# CAN_Interface.net
KiCad netlist of a schematic drawn in Altium Designer
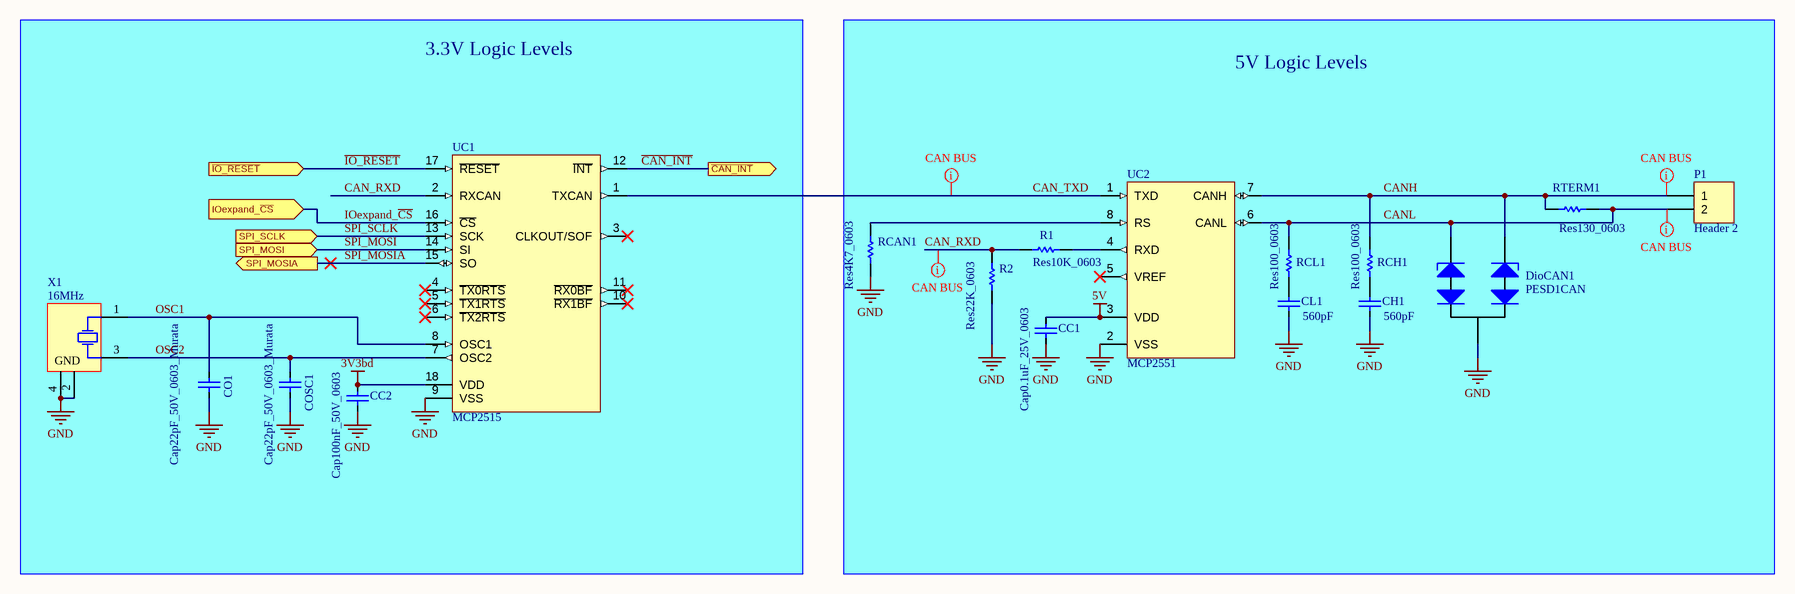
[diagram p0: CAN_Interface.SchDoc]

(export (version "E")
  (design (tool "Eeschema 10.0.6"))
  (components
    (comp (ref "CC1")
      (value "Cap0.1uF_25V_0603")
      (footprint "0603C_L")
      (libsource (lib " Advanced] Training Course - A365") (part "CAP General"))
    )
    (comp (ref "CC2")
      (value "Cap100nF_50V_0603")
      (footprint "0603C_L")
      (libsource (lib " Advanced] Training Course - A365") (part "CAP General"))
    )
    (comp (ref "CH1")
      (value "560pF")
      (footprint "0603C_L")
      (description "560pF 25V 0603")
      (fields (field (name "Comment") "CAP General"))
      (libsource (lib " Advanced] Training Course - A365") (part "CAP General"))
    )
    (comp (ref "CL1")
      (value "560pF")
      (footprint "0603C_L")
      (description "560pF 25V 0603")
      (fields (field (name "Comment") "CAP General"))
      (libsource (lib " Advanced] Training Course - A365") (part "CAP General"))
    )
    (comp (ref "CO1")
      (value "Cap22pF_50V_0603_Murata")
      (footprint "0603C_L")
      (fields (field (name "TOLERANCE") "5%"))
      (libsource (lib " Advanced] Training Course - A365") (part "CAP General"))
    )
    (comp (ref "COSC1")
      (value "Cap22pF_50V_0603_Murata")
      (footprint "0603C_L")
      (fields (field (name "TOLERANCE") "5%"))
      (libsource (lib " Advanced] Training Course - A365") (part "CAP General"))
    )
    (comp (ref "DioCAN1")
      (value "PESD1CAN")
      (footprint "SOT323")
      (description "Trans Voltage Suppressor Diode, 150W, 24V V(RWM), Bidirectional, 2 Element, Silicon")
      (fields (field (name "MANUFACTURER") "Nexperia USA Inc.") (field (name "SOURCE") "WCT.SchLib"))
      (libsource (lib " Advanced] Training Course - A365") (part "PESD1CAN"))
    )
    (comp (ref "P1")
      (value "Header 2")
      (footprint "HDR1X2")
      (description "Header, 2-Pin")
      (fields (field (name "PUBLISHER") "Altium Limited") (field (name "SOURCE") "WCT.SchLib"))
      (libsource (lib " Advanced] Training Course - A365") (part "Header 2"))
    )
    (comp (ref "R1")
      (value "Res10K_0603")
      (footprint "0603_L")
      (fields
        (field (name "MANUFACTURER") "Panasonic Electronic Components")
        (field (name "MANUFACTURER PART NUMBER") "ERJ-3GEYJ102V")
        (field (name "TOLERANCE") "5%")
        (field (name "SOURCE") "WCT.SchLib")
      )
      (libsource (lib " Advanced] Training Course - A365") (part "Resistor General"))
    )
    (comp (ref "R2")
      (value "Res22K_0603")
      (footprint "0603_L")
      (description "RES22K 0.5% 0603")
      (fields
        (field (name "MANUFACTURER") "Yageo")
        (field (name "MANUFACTURER PART NUMBER") "RT0603DRD0722KL")
        (field (name "SOURCE") "WCT.SchLib")
      )
      (libsource (lib " Advanced] Training Course - A365") (part "Resistor General"))
    )
    (comp (ref "RCAN1")
      (value "Res4K7_0603")
      (footprint "0603_L")
      (fields
        (field (name "MANUFACTURER") "Yageo")
        (field (name "TOLERANCE") "0.5%")
        (field (name "SOURCE") "WCT.SchLib")
      )
      (libsource (lib " Advanced] Training Course - A365") (part "Resistor General"))
    )
    (comp (ref "RCH1")
      (value "Res100_0603")
      (footprint "0603_L")
      (fields
        (field (name "MANUFACTURER") "Panasonic Electronic Components")
        (field (name "TOLERANCE") "5%")
        (field (name "SOURCE") "WCT.SchLib")
      )
      (libsource (lib " Advanced] Training Course - A365") (part "Resistor General"))
    )
    (comp (ref "RCL1")
      (value "Res100_0603")
      (footprint "0603_L")
      (fields
        (field (name "MANUFACTURER") "Panasonic Electronic Components")
        (field (name "TOLERANCE") "5%")
        (field (name "SOURCE") "WCT.SchLib")
      )
      (libsource (lib " Advanced] Training Course - A365") (part "Resistor General"))
    )
    (comp (ref "RTERM1")
      (value "Res130_0603")
      (footprint "0603_L")
      (fields
        (field (name "MANUFACTURER") "Panasonic Electronic Components")
        (field (name "TOLERANCE") "5%")
        (field (name "SOURCE") "WCT.SchLib")
      )
      (libsource (lib " Advanced] Training Course - A365") (part "Resistor General"))
    )
    (comp (ref "UC1")
      (value "MCP2515")
      (footprint "SOIC-SO18_M")
      (description "Stand-Alone CAN Controller With SPI Interface, 18-Pin SOIC, Extended Temperature")
      (fields
        (field (name "MANUFACTURER") "Microchip")
        (field (name "MANUFACTURER PART NUMBER") "MCP2515-E/SO")
        (field (name "AVAILABLE PREVIEW IMAGES") "2D")
        (field (name "SOURCE") "WCT.SchLib")
      )
      (libsource (lib " Advanced] Training Course - A365") (part "MCP2515"))
    )
    (comp (ref "UC2")
      (value "MCP2551")
      (footprint "SOIC-SN8_N")
      (description "High-Speed CAN Transceiver, 8-Pin SOIC, Extended Temperature")
      (fields
        (field (name "MANUFACTURER") "Microchip")
        (field (name "MANUFACTURER PART NUMBER") "MCP2551-E/SN")
        (field (name "AVAILABLE PREVIEW IMAGES") "2D")
        (field (name "SOURCE") "WCT.SchLib")
      )
      (libsource (lib " Advanced] Training Course - A365") (part "MCP2551"))
    )
    (comp (ref "X1")
      (value "Crystal 4Pin")
      (footprint "FP-ABM8-MFG")
      (description "Crystal 16MHz ±20ppm 18pF SMD-4 3.2mm x 2.5mm CSTCE16M0V53-R0 ABM8-16.000MHZ-B2-T")
      (fields
        (field (name "TOLERANCE") "20ppm")
        (field (name "FREQUENCY") "16MHz")
        (field (name "SOURCE") "WCT.SchLib")
      )
      (libsource (lib " Advanced] Training Course - A365") (part "Crystal 4Pin"))
    )
  )
  (nets
    (net (code "1") (name "/CANH") (class "Default")
      (node (ref "DioCAN1") (pin "1") (pinfunction "A_1") (pintype "passive"))
      (node (ref "P1") (pin "1") (pinfunction "1_1") (pintype "passive"))
      (node (ref "RCH1") (pin "2") (pinfunction "2_2") (pintype "passive"))
      (node (ref "RTERM1") (pin "2") (pinfunction "2_2") (pintype "passive"))
      (node (ref "UC2") (pin "7") (pinfunction "CANH_7") (pintype "bidirectional"))
    )
    (net (code "2") (name "/CANL") (class "Default")
      (node (ref "DioCAN1") (pin "2") (pinfunction "K_2") (pintype "passive"))
      (node (ref "P1") (pin "2") (pinfunction "2_2") (pintype "passive"))
      (node (ref "RCL1") (pin "2") (pinfunction "2_2") (pintype "passive"))
      (node (ref "RTERM1") (pin "1") (pinfunction "1_1") (pintype "passive"))
      (node (ref "UC2") (pin "6") (pinfunction "CANL_6") (pintype "bidirectional"))
    )
    (net (code "3") (name "/CAN_INT") (class "Default")
      (node (ref "UC1") (pin "12") (pinfunction "~{INT}_12") (pintype "output"))
    )
    (net (code "4") (name "/CAN_RXD") (class "Default")
      (node (ref "R1") (pin "2") (pinfunction "2_2") (pintype "passive"))
      (node (ref "R2") (pin "2") (pinfunction "2_2") (pintype "passive"))
      (node (ref "UC1") (pin "2") (pinfunction "RXCAN_2") (pintype "input"))
    )
    (net (code "5") (name "/CAN_TXD") (class "Default")
      (node (ref "UC1") (pin "1") (pinfunction "TXCAN_1") (pintype "output"))
      (node (ref "UC2") (pin "1") (pinfunction "TXD_1") (pintype "input"))
    )
    (net (code "6") (name "/IO_RESET") (class "Default")
      (node (ref "UC1") (pin "17") (pinfunction "~{RESET}_17") (pintype "input"))
    )
    (net (code "7") (name "/IOexpand_~{CS}") (class "Default")
      (node (ref "UC1") (pin "16") (pinfunction "~{CS}_16") (pintype "input"))
    )
    (net (code "8") (name "/OSC1") (class "Default")
      (node (ref "CO1") (pin "2") (pinfunction "2_2") (pintype "passive"))
      (node (ref "UC1") (pin "8") (pinfunction "OSC1_8") (pintype "input"))
      (node (ref "X1") (pin "1") (pinfunction "1_1") (pintype "passive"))
    )
    (net (code "9") (name "/OSC2") (class "Default")
      (node (ref "COSC1") (pin "2") (pinfunction "2_2") (pintype "passive"))
      (node (ref "UC1") (pin "7") (pinfunction "OSC2_7") (pintype "output"))
      (node (ref "X1") (pin "3") (pinfunction "3_3") (pintype "passive"))
    )
    (net (code "10") (name "/SPI_MOSI") (class "Default")
      (node (ref "UC1") (pin "14") (pinfunction "SI_14") (pintype "input"))
    )
    (net (code "11") (name "/SPI_MOSIA") (class "Default")
      (node (ref "UC1") (pin "15") (pinfunction "SO_15") (pintype "bidirectional"))
    )
    (net (code "12") (name "/SPI_SCLK") (class "Default")
      (node (ref "UC1") (pin "13") (pinfunction "SCK_13") (pintype "input"))
    )
    (net (code "13") (name "3V3bd") (class "Default")
      (node (ref "CC2") (pin "2") (pinfunction "2_2") (pintype "passive"))
      (node (ref "UC1") (pin "18") (pinfunction "VDD_18") (pintype "power_in"))
    )
    (net (code "14") (name "5V") (class "Default")
      (node (ref "CC1") (pin "2") (pinfunction "2_2") (pintype "passive"))
      (node (ref "UC2") (pin "3") (pinfunction "VDD_3") (pintype "power_in"))
    )
    (net (code "15") (name "GND") (class "Default")
      (node (ref "CC1") (pin "1") (pinfunction "1_1") (pintype "passive"))
      (node (ref "CC2") (pin "1") (pinfunction "1_1") (pintype "passive"))
      (node (ref "CH1") (pin "2") (pinfunction "2_2") (pintype "passive"))
      (node (ref "CL1") (pin "1") (pinfunction "1_1") (pintype "passive"))
      (node (ref "CO1") (pin "1") (pinfunction "1_1") (pintype "passive"))
      (node (ref "COSC1") (pin "1") (pinfunction "1_1") (pintype "passive"))
      (node (ref "DioCAN1") (pin "3") (pinfunction "3_3") (pintype "passive"))
      (node (ref "R2") (pin "1") (pinfunction "1_1") (pintype "passive"))
      (node (ref "RCAN1") (pin "1") (pinfunction "1_1") (pintype "passive"))
      (node (ref "UC1") (pin "9") (pinfunction "VSS_9") (pintype "power_in"))
      (node (ref "UC2") (pin "2") (pinfunction "VSS_2") (pintype "power_in"))
      (node (ref "X1") (pin "2") (pinfunction "GND_2") (pintype "power_in"))
      (node (ref "X1") (pin "4") (pinfunction "GND_4") (pintype "power_in"))
    )
    (net (code "16") (name "Net-(CH1-Pad1)") (class "Default")
      (node (ref "CH1") (pin "1") (pinfunction "1_1") (pintype "passive"))
      (node (ref "RCH1") (pin "1") (pinfunction "1_1") (pintype "passive"))
    )
    (net (code "17") (name "Net-(CL1-Pad2)") (class "Default")
      (node (ref "CL1") (pin "2") (pinfunction "2_2") (pintype "passive"))
      (node (ref "RCL1") (pin "1") (pinfunction "1_1") (pintype "passive"))
    )
    (net (code "18") (name "Net-(UC2-RS)") (class "Default")
      (node (ref "RCAN1") (pin "2") (pinfunction "2_2") (pintype "passive"))
      (node (ref "UC2") (pin "8") (pinfunction "RS_8") (pintype "input"))
    )
    (net (code "19") (name "Net-(UC2-RXD)") (class "Default")
      (node (ref "R1") (pin "1") (pinfunction "1_1") (pintype "passive"))
      (node (ref "UC2") (pin "4") (pinfunction "RXD_4") (pintype "output"))
    )
    (net (code "20") (name "unconnected-(UC1-CLKOUT{slash}SOF-Pad3)") (class "Default")
      (node (ref "UC1") (pin "3") (pinfunction "CLKOUT/SOF_3") (pintype "output+no_connect"))
    )
    (net (code "21") (name "unconnected-(UC1-~{RX0BF}-Pad11)") (class "Default")
      (node (ref "UC1") (pin "11") (pinfunction "~{RX0BF}_11") (pintype "output+no_connect"))
    )
    (net (code "22") (name "unconnected-(UC1-~{RX1BF}-Pad10)") (class "Default")
      (node (ref "UC1") (pin "10") (pinfunction "~{RX1BF}_10") (pintype "output+no_connect"))
    )
    (net (code "23") (name "unconnected-(UC1-~{TX0RTS}-Pad4)") (class "Default")
      (node (ref "UC1") (pin "4") (pinfunction "~{TX0RTS}_4") (pintype "input+no_connect"))
    )
    (net (code "24") (name "unconnected-(UC1-~{TX1RTS}-Pad5)") (class "Default")
      (node (ref "UC1") (pin "5") (pinfunction "~{TX1RTS}_5") (pintype "input+no_connect"))
    )
    (net (code "25") (name "unconnected-(UC1-~{TX2RTS}-Pad6)") (class "Default")
      (node (ref "UC1") (pin "6") (pinfunction "~{TX2RTS}_6") (pintype "input+no_connect"))
    )
    (net (code "26") (name "unconnected-(UC2-VREF-Pad5)") (class "Default")
      (node (ref "UC2") (pin "5") (pinfunction "VREF_5") (pintype "output+no_connect"))
    )
  )
)
